# LEscalierD.net
KiCad netlist of a schematic drawn in EAGLE
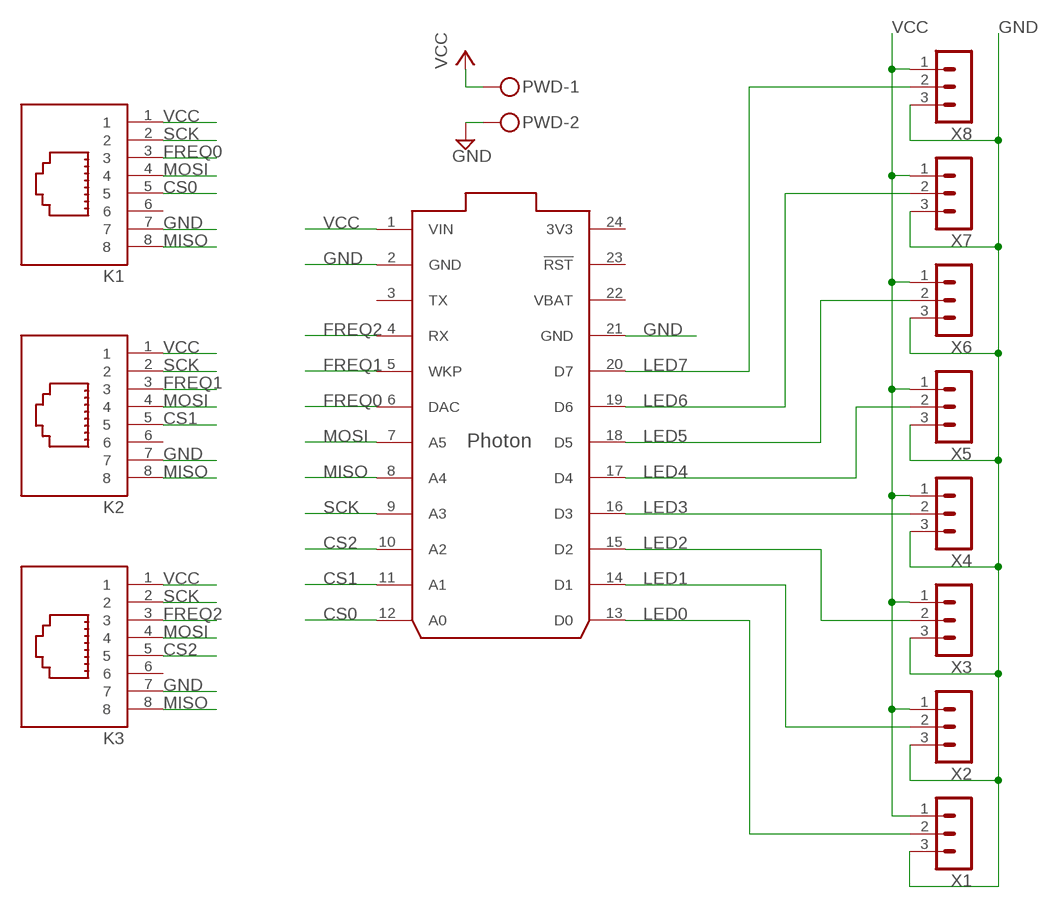
[diagram p0: schematic, sheet 1]

(export (version "E")
  (design (tool "Eeschema 10.0.6"))
  (components
    (comp (ref "K1")
      (value "615008144221")
      (footprint "eagle-import:615008144221")
      (libsource (lib "eagle-import") (part "615008144221"))
    )
    (comp (ref "K2")
      (value "615008144221")
      (footprint "eagle-import:615008144221")
      (libsource (lib "eagle-import") (part "615008144221"))
    )
    (comp (ref "K3")
      (value "615008144221")
      (footprint "eagle-import:615008144221")
      (libsource (lib "eagle-import") (part "615008144221"))
    )
    (comp (ref "PWD")
      (value "MKDSN1,5/2-5,08")
      (footprint "eagle-import:MKDSN1,5_2-5,08")
      (libsource (lib "eagle-import") (part "MKDSN1,5/2-5,08"))
    )
    (comp (ref "U1")
      (value "PHOTON_WITH_HEADERS")
      (footprint "eagle-import:PHOTON")
      (libsource (lib "eagle-import") (part "PHOTON_WITH_HEADERS"))
    )
    (comp (ref "X1")
      (value "B3B-XASTD")
      (footprint "eagle-import:B3B-XA")
      (libsource (lib "eagle-import") (part "B3B-XASTD"))
    )
    (comp (ref "X2")
      (value "B3B-XASTD")
      (footprint "eagle-import:B3B-XA")
      (libsource (lib "eagle-import") (part "B3B-XASTD"))
    )
    (comp (ref "X3")
      (value "B3B-XASTD")
      (footprint "eagle-import:B3B-XA")
      (libsource (lib "eagle-import") (part "B3B-XASTD"))
    )
    (comp (ref "X4")
      (value "B3B-XASTD")
      (footprint "eagle-import:B3B-XA")
      (libsource (lib "eagle-import") (part "B3B-XASTD"))
    )
    (comp (ref "X5")
      (value "B3B-XASTD")
      (footprint "eagle-import:B3B-XA")
      (libsource (lib "eagle-import") (part "B3B-XASTD"))
    )
    (comp (ref "X6")
      (value "B3B-XASTD")
      (footprint "eagle-import:B3B-XA")
      (libsource (lib "eagle-import") (part "B3B-XASTD"))
    )
    (comp (ref "X7")
      (value "B3B-XASTD")
      (footprint "eagle-import:B3B-XA")
      (libsource (lib "eagle-import") (part "B3B-XASTD"))
    )
    (comp (ref "X8")
      (value "B3B-XASTD")
      (footprint "eagle-import:B3B-XA")
      (libsource (lib "eagle-import") (part "B3B-XASTD"))
    )
  )
  (nets
    (net (code "1") (name "/3V3") (class "Default")
      (node (ref "U1") (pin "24") (pinfunction "3V3_24") (pintype "power_in"))
    )
    (net (code "2") (name "/CS0") (class "Default")
      (node (ref "K1") (pin "5") (pinfunction "5_5") (pintype "passive"))
      (node (ref "U1") (pin "12") (pinfunction "A0_12") (pintype "bidirectional"))
    )
    (net (code "3") (name "/CS1") (class "Default")
      (node (ref "K2") (pin "5") (pinfunction "5_5") (pintype "passive"))
      (node (ref "U1") (pin "11") (pinfunction "A1_11") (pintype "bidirectional"))
    )
    (net (code "4") (name "/CS2") (class "Default")
      (node (ref "K3") (pin "5") (pinfunction "5_5") (pintype "passive"))
      (node (ref "U1") (pin "10") (pinfunction "A2_10") (pintype "bidirectional"))
    )
    (net (code "5") (name "/FREQ0") (class "Default")
      (node (ref "K1") (pin "3") (pinfunction "3_3") (pintype "passive"))
      (node (ref "U1") (pin "6") (pinfunction "DAC_6") (pintype "bidirectional"))
    )
    (net (code "6") (name "/FREQ1") (class "Default")
      (node (ref "K2") (pin "3") (pinfunction "3_3") (pintype "passive"))
      (node (ref "U1") (pin "5") (pinfunction "WKP_5") (pintype "bidirectional"))
    )
    (net (code "7") (name "/FREQ2") (class "Default")
      (node (ref "K3") (pin "3") (pinfunction "3_3") (pintype "passive"))
      (node (ref "U1") (pin "4") (pinfunction "RX_4") (pintype "bidirectional"))
    )
    (net (code "8") (name "/LED0") (class "Default")
      (node (ref "U1") (pin "13") (pinfunction "D0_13") (pintype "bidirectional"))
      (node (ref "X1") (pin "2") (pinfunction "2_2") (pintype "passive"))
    )
    (net (code "9") (name "/LED1") (class "Default")
      (node (ref "U1") (pin "14") (pinfunction "D1_14") (pintype "bidirectional"))
      (node (ref "X2") (pin "2") (pinfunction "2_2") (pintype "passive"))
    )
    (net (code "10") (name "/LED2") (class "Default")
      (node (ref "U1") (pin "15") (pinfunction "D2_15") (pintype "bidirectional"))
      (node (ref "X3") (pin "2") (pinfunction "2_2") (pintype "passive"))
    )
    (net (code "11") (name "/LED3") (class "Default")
      (node (ref "U1") (pin "16") (pinfunction "D3_16") (pintype "bidirectional"))
      (node (ref "X4") (pin "2") (pinfunction "2_2") (pintype "passive"))
    )
    (net (code "12") (name "/LED4") (class "Default")
      (node (ref "U1") (pin "17") (pinfunction "D4_17") (pintype "bidirectional"))
      (node (ref "X5") (pin "2") (pinfunction "2_2") (pintype "passive"))
    )
    (net (code "13") (name "/LED5") (class "Default")
      (node (ref "U1") (pin "18") (pinfunction "D5_18") (pintype "bidirectional"))
      (node (ref "X6") (pin "2") (pinfunction "2_2") (pintype "passive"))
    )
    (net (code "14") (name "/LED6") (class "Default")
      (node (ref "U1") (pin "19") (pinfunction "D6_19") (pintype "bidirectional"))
      (node (ref "X7") (pin "2") (pinfunction "2_2") (pintype "passive"))
    )
    (net (code "15") (name "/LED7") (class "Default")
      (node (ref "U1") (pin "20") (pinfunction "D7_20") (pintype "bidirectional"))
      (node (ref "X8") (pin "2") (pinfunction "2_2") (pintype "passive"))
    )
    (net (code "16") (name "/MISO") (class "Default")
      (node (ref "K1") (pin "8") (pinfunction "8_8") (pintype "passive"))
      (node (ref "K2") (pin "8") (pinfunction "8_8") (pintype "passive"))
      (node (ref "K3") (pin "8") (pinfunction "8_8") (pintype "passive"))
      (node (ref "U1") (pin "8") (pinfunction "A4_8") (pintype "bidirectional"))
    )
    (net (code "17") (name "/MOSI") (class "Default")
      (node (ref "K1") (pin "4") (pinfunction "4_4") (pintype "passive"))
      (node (ref "K2") (pin "4") (pinfunction "4_4") (pintype "passive"))
      (node (ref "K3") (pin "4") (pinfunction "4_4") (pintype "passive"))
      (node (ref "U1") (pin "7") (pinfunction "A5_7") (pintype "bidirectional"))
    )
    (net (code "18") (name "/SCK") (class "Default")
      (node (ref "K1") (pin "2") (pinfunction "2_2") (pintype "passive"))
      (node (ref "K2") (pin "2") (pinfunction "2_2") (pintype "passive"))
      (node (ref "K3") (pin "2") (pinfunction "2_2") (pintype "passive"))
      (node (ref "U1") (pin "9") (pinfunction "A3_9") (pintype "bidirectional"))
    )
    (net (code "19") (name "/VBAT") (class "Default")
      (node (ref "U1") (pin "22") (pinfunction "VBAT_22") (pintype "power_in"))
    )
    (net (code "20") (name "GND") (class "Default")
      (node (ref "K1") (pin "7") (pinfunction "7_7") (pintype "passive"))
      (node (ref "K2") (pin "7") (pinfunction "7_7") (pintype "passive"))
      (node (ref "K3") (pin "7") (pinfunction "7_7") (pintype "passive"))
      (node (ref "PWD") (pin "2") (pinfunction "KL_2") (pintype "passive"))
      (node (ref "U1") (pin "2") (pinfunction "GND_2") (pintype "power_in"))
      (node (ref "U1") (pin "21") (pinfunction "GND_21") (pintype "power_in"))
      (node (ref "X1") (pin "3") (pinfunction "3_3") (pintype "passive"))
      (node (ref "X2") (pin "3") (pinfunction "3_3") (pintype "passive"))
      (node (ref "X3") (pin "3") (pinfunction "3_3") (pintype "passive"))
      (node (ref "X4") (pin "3") (pinfunction "3_3") (pintype "passive"))
      (node (ref "X5") (pin "3") (pinfunction "3_3") (pintype "passive"))
      (node (ref "X6") (pin "3") (pinfunction "3_3") (pintype "passive"))
      (node (ref "X7") (pin "3") (pinfunction "3_3") (pintype "passive"))
      (node (ref "X8") (pin "3") (pinfunction "3_3") (pintype "passive"))
    )
    (net (code "21") (name "VCC") (class "Default")
      (node (ref "K1") (pin "1") (pinfunction "1_1") (pintype "passive"))
      (node (ref "K2") (pin "1") (pinfunction "1_1") (pintype "passive"))
      (node (ref "K3") (pin "1") (pinfunction "1_1") (pintype "passive"))
      (node (ref "PWD") (pin "1") (pinfunction "KL_1") (pintype "passive"))
      (node (ref "U1") (pin "1") (pinfunction "VIN_1") (pintype "power_in"))
      (node (ref "X1") (pin "1") (pinfunction "1_1") (pintype "passive"))
      (node (ref "X2") (pin "1") (pinfunction "1_1") (pintype "passive"))
      (node (ref "X3") (pin "1") (pinfunction "1_1") (pintype "passive"))
      (node (ref "X4") (pin "1") (pinfunction "1_1") (pintype "passive"))
      (node (ref "X5") (pin "1") (pinfunction "1_1") (pintype "passive"))
      (node (ref "X6") (pin "1") (pinfunction "1_1") (pintype "passive"))
      (node (ref "X7") (pin "1") (pinfunction "1_1") (pintype "passive"))
      (node (ref "X8") (pin "1") (pinfunction "1_1") (pintype "passive"))
    )
    (net (code "22") (name "unconnected-(K1-Pad6)") (class "Default")
      (node (ref "K1") (pin "6") (pinfunction "6_6") (pintype "passive"))
    )
    (net (code "23") (name "unconnected-(K2-Pad6)") (class "Default")
      (node (ref "K2") (pin "6") (pinfunction "6_6") (pintype "passive"))
    )
    (net (code "24") (name "unconnected-(K3-Pad6)") (class "Default")
      (node (ref "K3") (pin "6") (pinfunction "6_6") (pintype "passive"))
    )
    (net (code "25") (name "unconnected-(U1-TX-Pad3)") (class "Default")
      (node (ref "U1") (pin "3") (pinfunction "TX_3") (pintype "bidirectional"))
    )
    (net (code "26") (name "unconnected-(U1-~{RST}-Pad23)") (class "Default")
      (node (ref "U1") (pin "23") (pinfunction "~{RST}_23") (pintype "bidirectional"))
    )
  )
)
